# Copy_of_min_system.net
KiCad netlist of a schematic drawn in Altium Designer
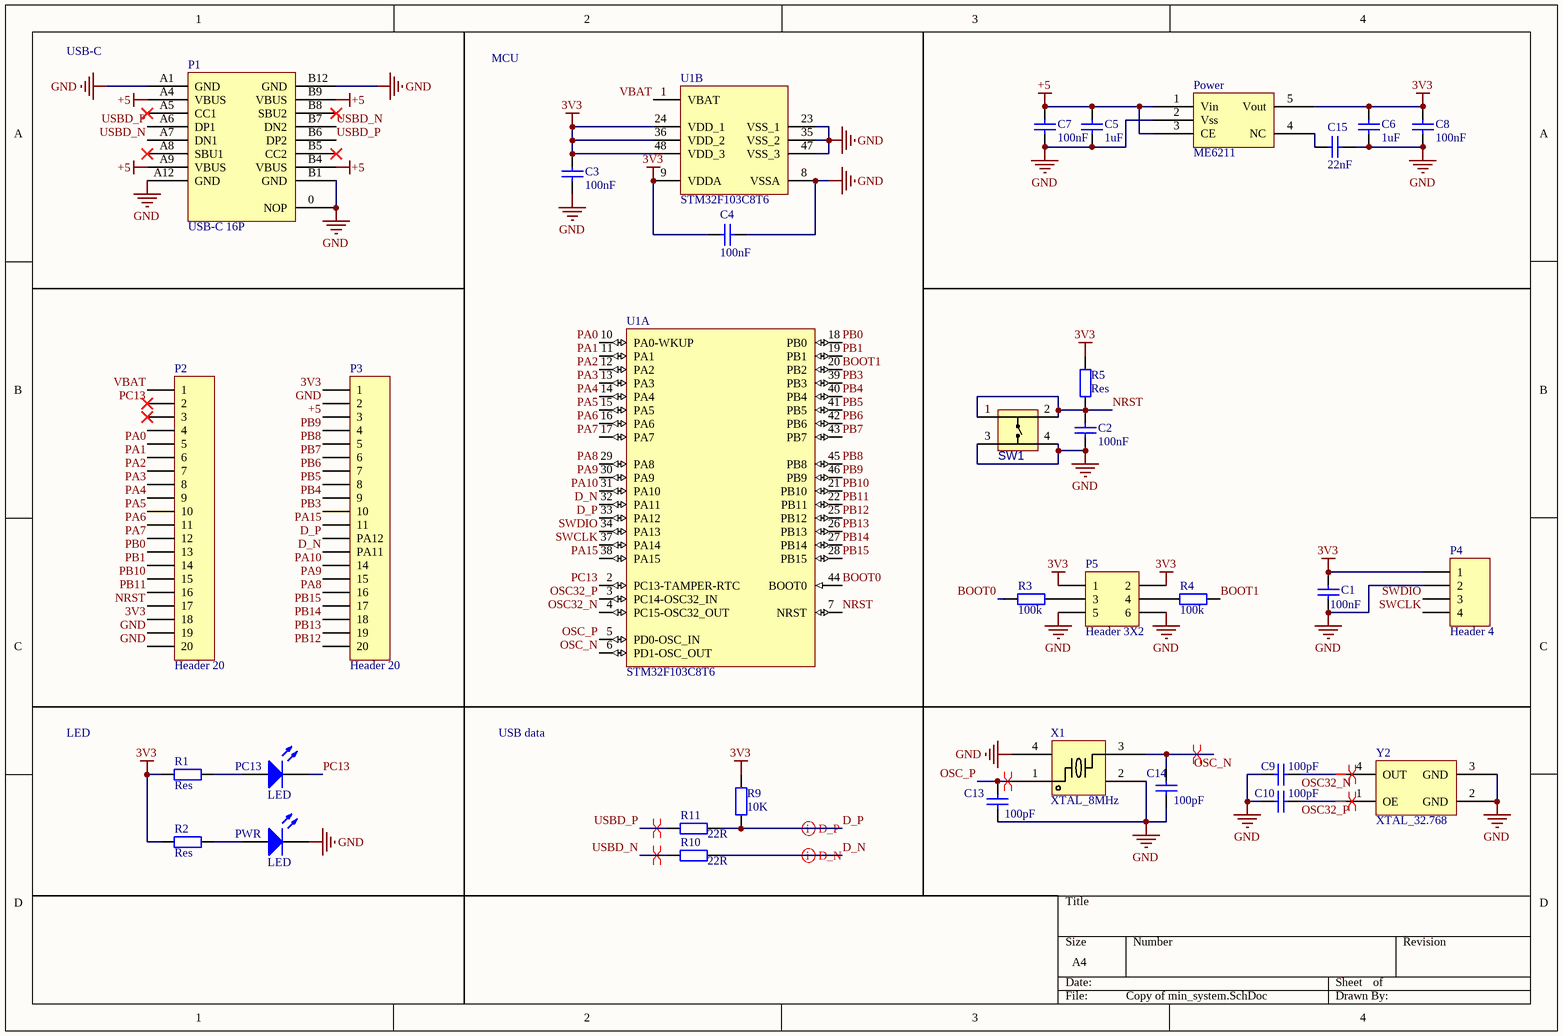
[diagram p0: Copy of min_system.SchDoc]

(export (version "E")
  (design (tool "Eeschema 10.0.6"))
  (components
    (comp (ref "C1")
      (value "100nF")
      (footprint "1608[0603]")
      (description "Capacitor")
      (fields (field (name "PUBLISHER") "Altium Limited"))
      (libsource (lib "Miscellaneous Devices") (part "Cap"))
    )
    (comp (ref "C2")
      (value "100nF")
      (footprint "1608[0603]")
      (description "Capacitor")
      (fields (field (name "PUBLISHER") "Altium Limited"))
      (libsource (lib "Miscellaneous Devices") (part "Cap"))
    )
    (comp (ref "C3")
      (value "100nF")
      (footprint "1608[0603]")
      (description "Capacitor")
      (fields (field (name "PUBLISHER") "Altium Limited"))
      (libsource (lib "Miscellaneous Devices") (part "Cap"))
    )
    (comp (ref "C4")
      (value "100nF")
      (footprint "1608[0603]")
      (description "Capacitor")
      (fields (field (name "PUBLISHER") "Altium Limited"))
      (libsource (lib "Miscellaneous Devices") (part "Cap"))
    )
    (comp (ref "C5")
      (value "1uF")
      (footprint "6-0805_M")
      (description "Capacitor")
      (fields (field (name "PUBLISHER") "Altium Limited"))
      (libsource (lib "Miscellaneous Devices") (part "Cap"))
    )
    (comp (ref "C6")
      (value "1uF")
      (footprint "6-0805_M")
      (description "Capacitor")
      (fields (field (name "PUBLISHER") "Altium Limited"))
      (libsource (lib "Miscellaneous Devices") (part "Cap"))
    )
    (comp (ref "C7")
      (value "100nF")
      (footprint "1608[0603]")
      (description "Capacitor")
      (fields (field (name "PUBLISHER") "Altium Limited"))
      (libsource (lib "Miscellaneous Devices") (part "Cap"))
    )
    (comp (ref "C8")
      (value "100nF")
      (footprint "1608[0603]")
      (description "Capacitor")
      (fields (field (name "PUBLISHER") "Altium Limited"))
      (libsource (lib "Miscellaneous Devices") (part "Cap"))
    )
    (comp (ref "C9")
      (value "100pF")
      (footprint "1608[0603]")
      (description "Capacitor")
      (fields (field (name "Comment") "Cap") (field (name "PUBLISHER") "Altium Limited"))
      (libsource (lib "Miscellaneous Devices") (part "Cap"))
    )
    (comp (ref "C10")
      (value "100pF")
      (footprint "1608[0603]")
      (description "Capacitor")
      (fields (field (name "Comment") "Cap") (field (name "PUBLISHER") "Altium Limited"))
      (libsource (lib "Miscellaneous Devices") (part "Cap"))
    )
    (comp (ref "C13")
      (value "100pF")
      (footprint "1608[0603]")
      (description "Capacitor")
      (fields (field (name "Comment") "Cap") (field (name "PUBLISHER") "Altium Limited"))
      (libsource (lib "Miscellaneous Devices") (part "Cap"))
    )
    (comp (ref "C14")
      (value "100pF")
      (footprint "1608[0603]")
      (description "Capacitor")
      (fields (field (name "Comment") "Cap") (field (name "PUBLISHER") "Altium Limited"))
      (libsource (lib "Miscellaneous Devices") (part "Cap"))
    )
    (comp (ref "C15")
      (value "22nF")
      (footprint "1608[0603]")
      (description "Capacitor")
      (fields (field (name "PUBLISHER") "Altium Limited"))
      (libsource (lib "Miscellaneous Devices") (part "Cap"))
    )
    (comp (ref "P1") (value "USB-C 16P") (footprint "USB-C 16P") (libsource (lib "USB") (part "USB-C 16P")))
    (comp (ref "P2")
      (value "Header 20")
      (footprint "HDR1X20")
      (description "Header, 20-Pin")
      (fields (field (name "PUBLISHER") "Altium Limited"))
      (libsource (lib "Miscellaneous Connectors") (part "Header 20"))
    )
    (comp (ref "P3")
      (value "Header 20")
      (footprint "HDR1X20")
      (description "Header, 20-Pin")
      (fields (field (name "PUBLISHER") "Altium Limited"))
      (libsource (lib "Miscellaneous Connectors") (part "Header 20"))
    )
    (comp (ref "P4")
      (value "Header 4")
      (footprint "HDR1X4")
      (description "Header, 4-Pin")
      (fields (field (name "PUBLISHER") "Altium Limited"))
      (libsource (lib "Miscellaneous Connectors") (part "Header 4"))
    )
    (comp (ref "P5")
      (value "Header 3X2")
      (footprint "HDR2X3")
      (description "Header, 3-Pin, Dual row")
      (fields (field (name "PUBLISHER") "Altium Limited"))
      (libsource (lib "Miscellaneous Connectors") (part "Header 3X2"))
    )
    (comp (ref "PC13")
      (value "LED")
      (footprint "LED_0603")
      (description "Typical INFRARED GaAs LED")
      (fields (field (name "PUBLISHER") "Altium Limited"))
      (libsource (lib "Miscellaneous Devices") (part "LED"))
    )
    (comp (ref "Power")
      (value "ME6211")
      (footprint "ME6211")
      (description "SOT23-5")
      (libsource (lib "Common_Modules") (part "ME6211"))
    )
    (comp (ref "PWR")
      (value "LED")
      (footprint "LED_0603")
      (description "Typical INFRARED GaAs LED")
      (fields (field (name "PUBLISHER") "Altium Limited"))
      (libsource (lib "Miscellaneous Devices") (part "LED"))
    )
    (comp (ref "R1")
      (value "Res")
      (footprint "1608[0603]")
      (description "Resistor")
      (fields (field (name "PUBLISHER") "Altium Limited"))
      (libsource (lib "") (part "Res_1"))
    )
    (comp (ref "R2")
      (value "Res")
      (footprint "1608[0603]")
      (description "Resistor")
      (fields (field (name "PUBLISHER") "Altium Limited"))
      (libsource (lib "") (part "Res_1"))
    )
    (comp (ref "R3")
      (value "100k")
      (footprint "1608[0603]")
      (description "Resistor")
      (fields (field (name "PUBLISHER") "Altium Limited"))
      (libsource (lib "") (part "Res_1"))
    )
    (comp (ref "R4")
      (value "100k")
      (footprint "1608[0603]")
      (description "Resistor")
      (fields (field (name "PUBLISHER") "Altium Limited"))
      (libsource (lib "") (part "Res_1"))
    )
    (comp (ref "R5")
      (value "Res")
      (footprint "1608[0603]")
      (description "Resistor")
      (fields (field (name "PUBLISHER") "Altium Limited"))
      (libsource (lib "") (part "Res_2"))
    )
    (comp (ref "R9")
      (value "10K")
      (footprint "1608[0603]")
      (description "Resistor")
      (fields (field (name "PUBLISHER") "Altium Limited"))
      (libsource (lib "Miscellaneous Devices") (part "Res"))
    )
    (comp (ref "R10")
      (value "22R")
      (footprint "1608[0603]")
      (description "Resistor")
      (fields (field (name "PUBLISHER") "Altium Limited"))
      (libsource (lib "") (part "Res_1"))
    )
    (comp (ref "R11")
      (value "22R")
      (footprint "1608[0603]")
      (description "Resistor")
      (fields (field (name "PUBLISHER") "Altium Limited"))
      (libsource (lib "") (part "Res_1"))
    )
    (comp (ref "SW1")
      (value "TS-1089S-AR02516")
      (footprint "Button-SMD_4P")
      (description "SMD_4P-L4.2-W3.3-P2.15-LS5.1")
      (fields (field (name "MANUFACTURER") "XUNPU(讯普)"))
      (libsource (lib "Miscellaneous Devices") (part "Button-SMD_4P"))
    )
    (comp (ref "U1")
      (value "STM32F103C8T6")
      (footprint "STM-LQFP48_N")
      (libsource (lib "STMicroelectronics STM32 F1") (part "STM32F103C8T6"))
    )
    (comp (ref "X1")
      (value "XTAL_8MHz")
      (footprint "Miscellaneous Devices:XTAL_3225")
      (libsource (lib "Miscellaneous Devices") (part "XTAL_3225"))
    )
    (comp (ref "Y2")
      (value "XTAL_32.768")
      (footprint "MC-306")
      (description "32.768kHz")
      (fields (field (name "PUBLISHER") "Altium Limited"))
      (libsource (lib "Miscellaneous Devices") (part "XTAL_32.768"))
    )
  )
  (nets
    (net (code "1") (name "+5") (class "Default")
      (node (ref "C5") (pin "2") (pinfunction "2_2") (pintype "passive"))
      (node (ref "C7") (pin "2") (pinfunction "2_2") (pintype "passive"))
      (node (ref "P1") (pin "A4") (pinfunction "VBUS_A4") (pintype "passive"))
      (node (ref "P1") (pin "A9") (pinfunction "VBUS_A9") (pintype "passive"))
      (node (ref "P1") (pin "B4") (pinfunction "VBUS_B4") (pintype "passive"))
      (node (ref "P1") (pin "B9") (pinfunction "VBUS_B9") (pintype "passive"))
      (node (ref "P3") (pin "3") (pinfunction "3_3") (pintype "passive"))
      (node (ref "Power") (pin "1") (pinfunction "Vin_1") (pintype "passive"))
      (node (ref "Power") (pin "3") (pinfunction "CE_3") (pintype "passive"))
    )
    (net (code "2") (name "/BOOT0") (class "Default")
      (node (ref "R3") (pin "1") (pinfunction "1_1") (pintype "passive"))
      (node (ref "U1") (pin "44") (pinfunction "BOOT0_44") (pintype "input"))
    )
    (net (code "3") (name "/BOOT1") (class "Default")
      (node (ref "R4") (pin "2") (pinfunction "2_2") (pintype "passive"))
      (node (ref "U1") (pin "20") (pinfunction "PB2_20") (pintype "bidirectional"))
    )
    (net (code "4") (name "/D_N") (class "Default")
      (node (ref "P3") (pin "13") (pinfunction "13_13") (pintype "passive"))
      (node (ref "R10") (pin "2") (pinfunction "2_2") (pintype "passive"))
      (node (ref "U1") (pin "32") (pinfunction "PA11_32") (pintype "bidirectional"))
    )
    (net (code "5") (name "/D_P") (class "Default")
      (node (ref "P3") (pin "12") (pinfunction "12_12") (pintype "passive"))
      (node (ref "R11") (pin "2") (pinfunction "2_2") (pintype "passive"))
      (node (ref "R9") (pin "2") (pinfunction "2_2") (pintype "passive"))
      (node (ref "U1") (pin "33") (pinfunction "PA12_33") (pintype "bidirectional"))
    )
    (net (code "6") (name "/NRST") (class "Default")
      (node (ref "C2") (pin "2") (pinfunction "2_2") (pintype "passive"))
      (node (ref "P2") (pin "17") (pinfunction "17_17") (pintype "passive"))
      (node (ref "R5") (pin "1") (pinfunction "1_1") (pintype "passive"))
      (node (ref "SW1") (pin "1") (pinfunction "1_1") (pintype "passive"))
      (node (ref "SW1") (pin "2") (pinfunction "2_2") (pintype "passive"))
      (node (ref "U1") (pin "7") (pinfunction "NRST_7") (pintype "bidirectional"))
    )
    (net (code "7") (name "/OSC32_N") (class "Default")
      (node (ref "C9") (pin "1") (pinfunction "1_1") (pintype "passive"))
      (node (ref "U1") (pin "4") (pinfunction "PC15-OSC32_OUT_4") (pintype "bidirectional"))
      (node (ref "Y2") (pin "4") (pinfunction "OUT_4") (pintype "passive"))
    )
    (net (code "8") (name "/OSC32_P") (class "Default")
      (node (ref "C10") (pin "2") (pinfunction "2_2") (pintype "passive"))
      (node (ref "U1") (pin "3") (pinfunction "PC14-OSC32_IN_3") (pintype "bidirectional"))
      (node (ref "Y2") (pin "1") (pinfunction "OE_1") (pintype "passive"))
    )
    (net (code "9") (name "/OSC_N") (class "Default")
      (node (ref "C14") (pin "2") (pinfunction "2_2") (pintype "passive"))
      (node (ref "U1") (pin "6") (pinfunction "PD1-OSC_OUT_6") (pintype "bidirectional"))
      (node (ref "X1") (pin "3") (pinfunction "3_3") (pintype "passive"))
    )
    (net (code "10") (name "/OSC_P") (class "Default")
      (node (ref "C13") (pin "1") (pinfunction "1_1") (pintype "passive"))
      (node (ref "U1") (pin "5") (pinfunction "PD0-OSC_IN_5") (pintype "bidirectional"))
      (node (ref "X1") (pin "1") (pinfunction "1_1") (pintype "passive"))
    )
    (net (code "11") (name "/PA0") (class "Default")
      (node (ref "P2") (pin "5") (pinfunction "5_5") (pintype "passive"))
      (node (ref "U1") (pin "10") (pinfunction "PA0-WKUP_10") (pintype "bidirectional"))
    )
    (net (code "12") (name "/PA1") (class "Default")
      (node (ref "P2") (pin "6") (pinfunction "6_6") (pintype "passive"))
      (node (ref "U1") (pin "11") (pinfunction "PA1_11") (pintype "bidirectional"))
    )
    (net (code "13") (name "/PA2") (class "Default")
      (node (ref "P2") (pin "7") (pinfunction "7_7") (pintype "passive"))
      (node (ref "U1") (pin "12") (pinfunction "PA2_12") (pintype "bidirectional"))
    )
    (net (code "14") (name "/PA3") (class "Default")
      (node (ref "P2") (pin "8") (pinfunction "8_8") (pintype "passive"))
      (node (ref "U1") (pin "13") (pinfunction "PA3_13") (pintype "bidirectional"))
    )
    (net (code "15") (name "/PA4") (class "Default")
      (node (ref "P2") (pin "9") (pinfunction "9_9") (pintype "passive"))
      (node (ref "U1") (pin "14") (pinfunction "PA4_14") (pintype "bidirectional"))
    )
    (net (code "16") (name "/PA5") (class "Default")
      (node (ref "P2") (pin "10") (pinfunction "10_10") (pintype "passive"))
      (node (ref "U1") (pin "15") (pinfunction "PA5_15") (pintype "bidirectional"))
    )
    (net (code "17") (name "/PA6") (class "Default")
      (node (ref "P2") (pin "11") (pinfunction "11_11") (pintype "passive"))
      (node (ref "U1") (pin "16") (pinfunction "PA6_16") (pintype "bidirectional"))
    )
    (net (code "18") (name "/PA7") (class "Default")
      (node (ref "P2") (pin "12") (pinfunction "12_12") (pintype "passive"))
      (node (ref "U1") (pin "17") (pinfunction "PA7_17") (pintype "bidirectional"))
    )
    (net (code "19") (name "/PA8") (class "Default")
      (node (ref "P3") (pin "16") (pinfunction "16_16") (pintype "passive"))
      (node (ref "U1") (pin "29") (pinfunction "PA8_29") (pintype "bidirectional"))
    )
    (net (code "20") (name "/PA9") (class "Default")
      (node (ref "P3") (pin "15") (pinfunction "15_15") (pintype "passive"))
      (node (ref "U1") (pin "30") (pinfunction "PA9_30") (pintype "bidirectional"))
    )
    (net (code "21") (name "/PA10") (class "Default")
      (node (ref "P3") (pin "14") (pinfunction "14_14") (pintype "passive"))
      (node (ref "U1") (pin "31") (pinfunction "PA10_31") (pintype "bidirectional"))
    )
    (net (code "22") (name "/PA15") (class "Default")
      (node (ref "P3") (pin "11") (pinfunction "11_11") (pintype "passive"))
      (node (ref "U1") (pin "38") (pinfunction "PA15_38") (pintype "bidirectional"))
    )
    (net (code "23") (name "/PB0") (class "Default")
      (node (ref "P2") (pin "13") (pinfunction "13_13") (pintype "passive"))
      (node (ref "U1") (pin "18") (pinfunction "PB0_18") (pintype "bidirectional"))
    )
    (net (code "24") (name "/PB1") (class "Default")
      (node (ref "P2") (pin "14") (pinfunction "14_14") (pintype "passive"))
      (node (ref "U1") (pin "19") (pinfunction "PB1_19") (pintype "bidirectional"))
    )
    (net (code "25") (name "/PB3") (class "Default")
      (node (ref "P3") (pin "10") (pinfunction "10_10") (pintype "passive"))
      (node (ref "U1") (pin "39") (pinfunction "PB3_39") (pintype "bidirectional"))
    )
    (net (code "26") (name "/PB4") (class "Default")
      (node (ref "P3") (pin "9") (pinfunction "9_9") (pintype "passive"))
      (node (ref "U1") (pin "40") (pinfunction "PB4_40") (pintype "bidirectional"))
    )
    (net (code "27") (name "/PB5") (class "Default")
      (node (ref "P3") (pin "8") (pinfunction "8_8") (pintype "passive"))
      (node (ref "U1") (pin "41") (pinfunction "PB5_41") (pintype "bidirectional"))
    )
    (net (code "28") (name "/PB6") (class "Default")
      (node (ref "P3") (pin "7") (pinfunction "7_7") (pintype "passive"))
      (node (ref "U1") (pin "42") (pinfunction "PB6_42") (pintype "bidirectional"))
    )
    (net (code "29") (name "/PB7") (class "Default")
      (node (ref "P3") (pin "6") (pinfunction "6_6") (pintype "passive"))
      (node (ref "U1") (pin "43") (pinfunction "PB7_43") (pintype "bidirectional"))
    )
    (net (code "30") (name "/PB8") (class "Default")
      (node (ref "P3") (pin "5") (pinfunction "5_5") (pintype "passive"))
      (node (ref "U1") (pin "45") (pinfunction "PB8_45") (pintype "bidirectional"))
    )
    (net (code "31") (name "/PB9") (class "Default")
      (node (ref "P3") (pin "4") (pinfunction "4_4") (pintype "passive"))
      (node (ref "U1") (pin "46") (pinfunction "PB9_46") (pintype "bidirectional"))
    )
    (net (code "32") (name "/PB10") (class "Default")
      (node (ref "P2") (pin "15") (pinfunction "15_15") (pintype "passive"))
      (node (ref "U1") (pin "21") (pinfunction "PB10_21") (pintype "bidirectional"))
    )
    (net (code "33") (name "/PB11") (class "Default")
      (node (ref "P2") (pin "16") (pinfunction "16_16") (pintype "passive"))
      (node (ref "U1") (pin "22") (pinfunction "PB11_22") (pintype "bidirectional"))
    )
    (net (code "34") (name "/PB12") (class "Default")
      (node (ref "P3") (pin "20") (pinfunction "20_20") (pintype "passive"))
      (node (ref "U1") (pin "25") (pinfunction "PB12_25") (pintype "bidirectional"))
    )
    (net (code "35") (name "/PB13") (class "Default")
      (node (ref "P3") (pin "19") (pinfunction "19_19") (pintype "passive"))
      (node (ref "U1") (pin "26") (pinfunction "PB13_26") (pintype "bidirectional"))
    )
    (net (code "36") (name "/PB14") (class "Default")
      (node (ref "P3") (pin "18") (pinfunction "18_18") (pintype "passive"))
      (node (ref "U1") (pin "27") (pinfunction "PB14_27") (pintype "bidirectional"))
    )
    (net (code "37") (name "/PB15") (class "Default")
      (node (ref "P3") (pin "17") (pinfunction "17_17") (pintype "passive"))
      (node (ref "U1") (pin "28") (pinfunction "PB15_28") (pintype "bidirectional"))
    )
    (net (code "38") (name "/PC13") (class "Default")
      (node (ref "P2") (pin "2") (pinfunction "2_2") (pintype "passive"))
      (node (ref "PC13") (pin "2") (pinfunction "K_2") (pintype "passive"))
      (node (ref "U1") (pin "2") (pinfunction "PC13-TAMPER-RTC_2") (pintype "bidirectional"))
    )
    (net (code "39") (name "/SWCLK") (class "Default")
      (node (ref "P4") (pin "4") (pinfunction "4_4") (pintype "passive"))
      (node (ref "U1") (pin "37") (pinfunction "PA14_37") (pintype "bidirectional"))
    )
    (net (code "40") (name "/SWDIO") (class "Default")
      (node (ref "P4") (pin "3") (pinfunction "3_3") (pintype "passive"))
      (node (ref "U1") (pin "34") (pinfunction "PA13_34") (pintype "bidirectional"))
    )
    (net (code "41") (name "/USBD_N") (class "Default")
      (node (ref "P1") (pin "A7") (pinfunction "DN1_A7") (pintype "passive"))
      (node (ref "P1") (pin "B7") (pinfunction "DN2_B7") (pintype "passive"))
      (node (ref "R10") (pin "1") (pinfunction "1_1") (pintype "passive"))
    )
    (net (code "42") (name "/USBD_P") (class "Default")
      (node (ref "P1") (pin "A6") (pinfunction "DP1_A6") (pintype "passive"))
      (node (ref "P1") (pin "B6") (pinfunction "DP2_B6") (pintype "passive"))
      (node (ref "R11") (pin "1") (pinfunction "1_1") (pintype "passive"))
    )
    (net (code "43") (name "/VBAT") (class "Default")
      (node (ref "P2") (pin "1") (pinfunction "1_1") (pintype "passive"))
      (node (ref "U1") (pin "1") (pinfunction "VBAT_1") (pintype "power_in"))
    )
    (net (code "44") (name "3V3") (class "Default")
      (node (ref "C1") (pin "2") (pinfunction "2_2") (pintype "passive"))
      (node (ref "C3") (pin "2") (pinfunction "2_2") (pintype "passive"))
      (node (ref "C4") (pin "2") (pinfunction "2_2") (pintype "passive"))
      (node (ref "C6") (pin "2") (pinfunction "2_2") (pintype "passive"))
      (node (ref "C8") (pin "2") (pinfunction "2_2") (pintype "passive"))
      (node (ref "P2") (pin "18") (pinfunction "18_18") (pintype "passive"))
      (node (ref "P3") (pin "1") (pinfunction "1_1") (pintype "passive"))
      (node (ref "P4") (pin "1") (pinfunction "1_1") (pintype "passive"))
      (node (ref "P5") (pin "1") (pinfunction "1_1") (pintype "passive"))
      (node (ref "P5") (pin "2") (pinfunction "2_2") (pintype "passive"))
      (node (ref "Power") (pin "5") (pinfunction "Vout_5") (pintype "passive"))
      (node (ref "R1") (pin "1") (pinfunction "1_1") (pintype "passive"))
      (node (ref "R2") (pin "1") (pinfunction "1_1") (pintype "passive"))
      (node (ref "R5") (pin "2") (pinfunction "2_2") (pintype "passive"))
      (node (ref "R9") (pin "1") (pinfunction "1_1") (pintype "passive"))
      (node (ref "U1") (pin "24") (pinfunction "VDD_1_24") (pintype "power_in"))
      (node (ref "U1") (pin "36") (pinfunction "VDD_2_36") (pintype "power_in"))
      (node (ref "U1") (pin "48") (pinfunction "VDD_3_48") (pintype "power_in"))
      (node (ref "U1") (pin "9") (pinfunction "VDDA_9") (pintype "power_in"))
    )
    (net (code "45") (name "GND") (class "Default")
      (node (ref "C1") (pin "1") (pinfunction "1_1") (pintype "passive"))
      (node (ref "C10") (pin "1") (pinfunction "1_1") (pintype "passive"))
      (node (ref "C13") (pin "2") (pinfunction "2_2") (pintype "passive"))
      (node (ref "C14") (pin "1") (pinfunction "1_1") (pintype "passive"))
      (node (ref "C15") (pin "2") (pinfunction "2_2") (pintype "passive"))
      (node (ref "C2") (pin "1") (pinfunction "1_1") (pintype "passive"))
      (node (ref "C3") (pin "1") (pinfunction "1_1") (pintype "passive"))
      (node (ref "C4") (pin "1") (pinfunction "1_1") (pintype "passive"))
      (node (ref "C5") (pin "1") (pinfunction "1_1") (pintype "passive"))
      (node (ref "C6") (pin "1") (pinfunction "1_1") (pintype "passive"))
      (node (ref "C7") (pin "1") (pinfunction "1_1") (pintype "passive"))
      (node (ref "C8") (pin "1") (pinfunction "1_1") (pintype "passive"))
      (node (ref "C9") (pin "2") (pinfunction "2_2") (pintype "passive"))
      (node (ref "P1") (pin "0") (pinfunction "NOP_0") (pintype "passive"))
      (node (ref "P1") (pin "A1") (pinfunction "GND_A1") (pintype "passive"))
      (node (ref "P1") (pin "A12") (pinfunction "GND_A12") (pintype "passive"))
      (node (ref "P1") (pin "B1") (pinfunction "GND_B1") (pintype "passive"))
      (node (ref "P1") (pin "B12") (pinfunction "GND_B12") (pintype "passive"))
      (node (ref "P2") (pin "19") (pinfunction "19_19") (pintype "passive"))
      (node (ref "P2") (pin "20") (pinfunction "20_20") (pintype "passive"))
      (node (ref "P3") (pin "2") (pinfunction "2_2") (pintype "passive"))
      (node (ref "P4") (pin "2") (pinfunction "2_2") (pintype "passive"))
      (node (ref "P5") (pin "5") (pinfunction "5_5") (pintype "passive"))
      (node (ref "P5") (pin "6") (pinfunction "6_6") (pintype "passive"))
      (node (ref "PWR") (pin "2") (pinfunction "K_2") (pintype "passive"))
      (node (ref "Power") (pin "2") (pinfunction "Vss_2") (pintype "passive"))
      (node (ref "SW1") (pin "3") (pinfunction "3_3") (pintype "passive"))
      (node (ref "SW1") (pin "4") (pinfunction "4_4") (pintype "passive"))
      (node (ref "U1") (pin "23") (pinfunction "VSS_1_23") (pintype "power_in"))
      (node (ref "U1") (pin "35") (pinfunction "VSS_2_35") (pintype "power_in"))
      (node (ref "U1") (pin "47") (pinfunction "VSS_3_47") (pintype "power_in"))
      (node (ref "U1") (pin "8") (pinfunction "VSSA_8") (pintype "power_in"))
      (node (ref "X1") (pin "2") (pinfunction "2_2") (pintype "passive"))
      (node (ref "X1") (pin "4") (pinfunction "4_4") (pintype "passive"))
      (node (ref "Y2") (pin "2") (pinfunction "GND_2") (pintype "passive"))
      (node (ref "Y2") (pin "3") (pinfunction "GND_3") (pintype "passive"))
    )
    (net (code "46") (name "Net-(P5-Pad3)") (class "Default")
      (node (ref "P5") (pin "3") (pinfunction "3_3") (pintype "passive"))
      (node (ref "R3") (pin "2") (pinfunction "2_2") (pintype "passive"))
    )
    (net (code "47") (name "Net-(P5-Pad4)") (class "Default")
      (node (ref "P5") (pin "4") (pinfunction "4_4") (pintype "passive"))
      (node (ref "R4") (pin "1") (pinfunction "1_1") (pintype "passive"))
    )
    (net (code "48") (name "Net-(PC13-A)") (class "Default")
      (node (ref "PC13") (pin "1") (pinfunction "A_1") (pintype "passive"))
      (node (ref "R1") (pin "2") (pinfunction "2_2") (pintype "passive"))
    )
    (net (code "49") (name "Net-(PWR-A)") (class "Default")
      (node (ref "PWR") (pin "1") (pinfunction "A_1") (pintype "passive"))
      (node (ref "R2") (pin "2") (pinfunction "2_2") (pintype "passive"))
    )
    (net (code "50") (name "Net-(Power-NC)") (class "Default")
      (node (ref "C15") (pin "1") (pinfunction "1_1") (pintype "passive"))
      (node (ref "Power") (pin "4") (pinfunction "NC_4") (pintype "passive"))
    )
    (net (code "51") (name "unconnected-(P1-CC1-PadA5)") (class "Default")
      (node (ref "P1") (pin "A5") (pinfunction "CC1_A5") (pintype "passive+no_connect"))
    )
    (net (code "52") (name "unconnected-(P1-CC2-PadB5)") (class "Default")
      (node (ref "P1") (pin "B5") (pinfunction "CC2_B5") (pintype "passive+no_connect"))
    )
    (net (code "53") (name "unconnected-(P1-SBU1-PadA8)") (class "Default")
      (node (ref "P1") (pin "A8") (pinfunction "SBU1_A8") (pintype "passive+no_connect"))
    )
    (net (code "54") (name "unconnected-(P1-SBU2-PadB8)") (class "Default")
      (node (ref "P1") (pin "B8") (pinfunction "SBU2_B8") (pintype "passive+no_connect"))
    )
    (net (code "55") (name "unconnected-(P2-Pad3)") (class "Default")
      (node (ref "P2") (pin "3") (pinfunction "3_3") (pintype "passive+no_connect"))
    )
    (net (code "56") (name "unconnected-(P2-Pad4)") (class "Default")
      (node (ref "P2") (pin "4") (pinfunction "4_4") (pintype "passive"))
    )
  )
)
